# SSB_Transceiver_TX-RX-Switch.net
KiCad netlist of a schematic drawn in EAGLE
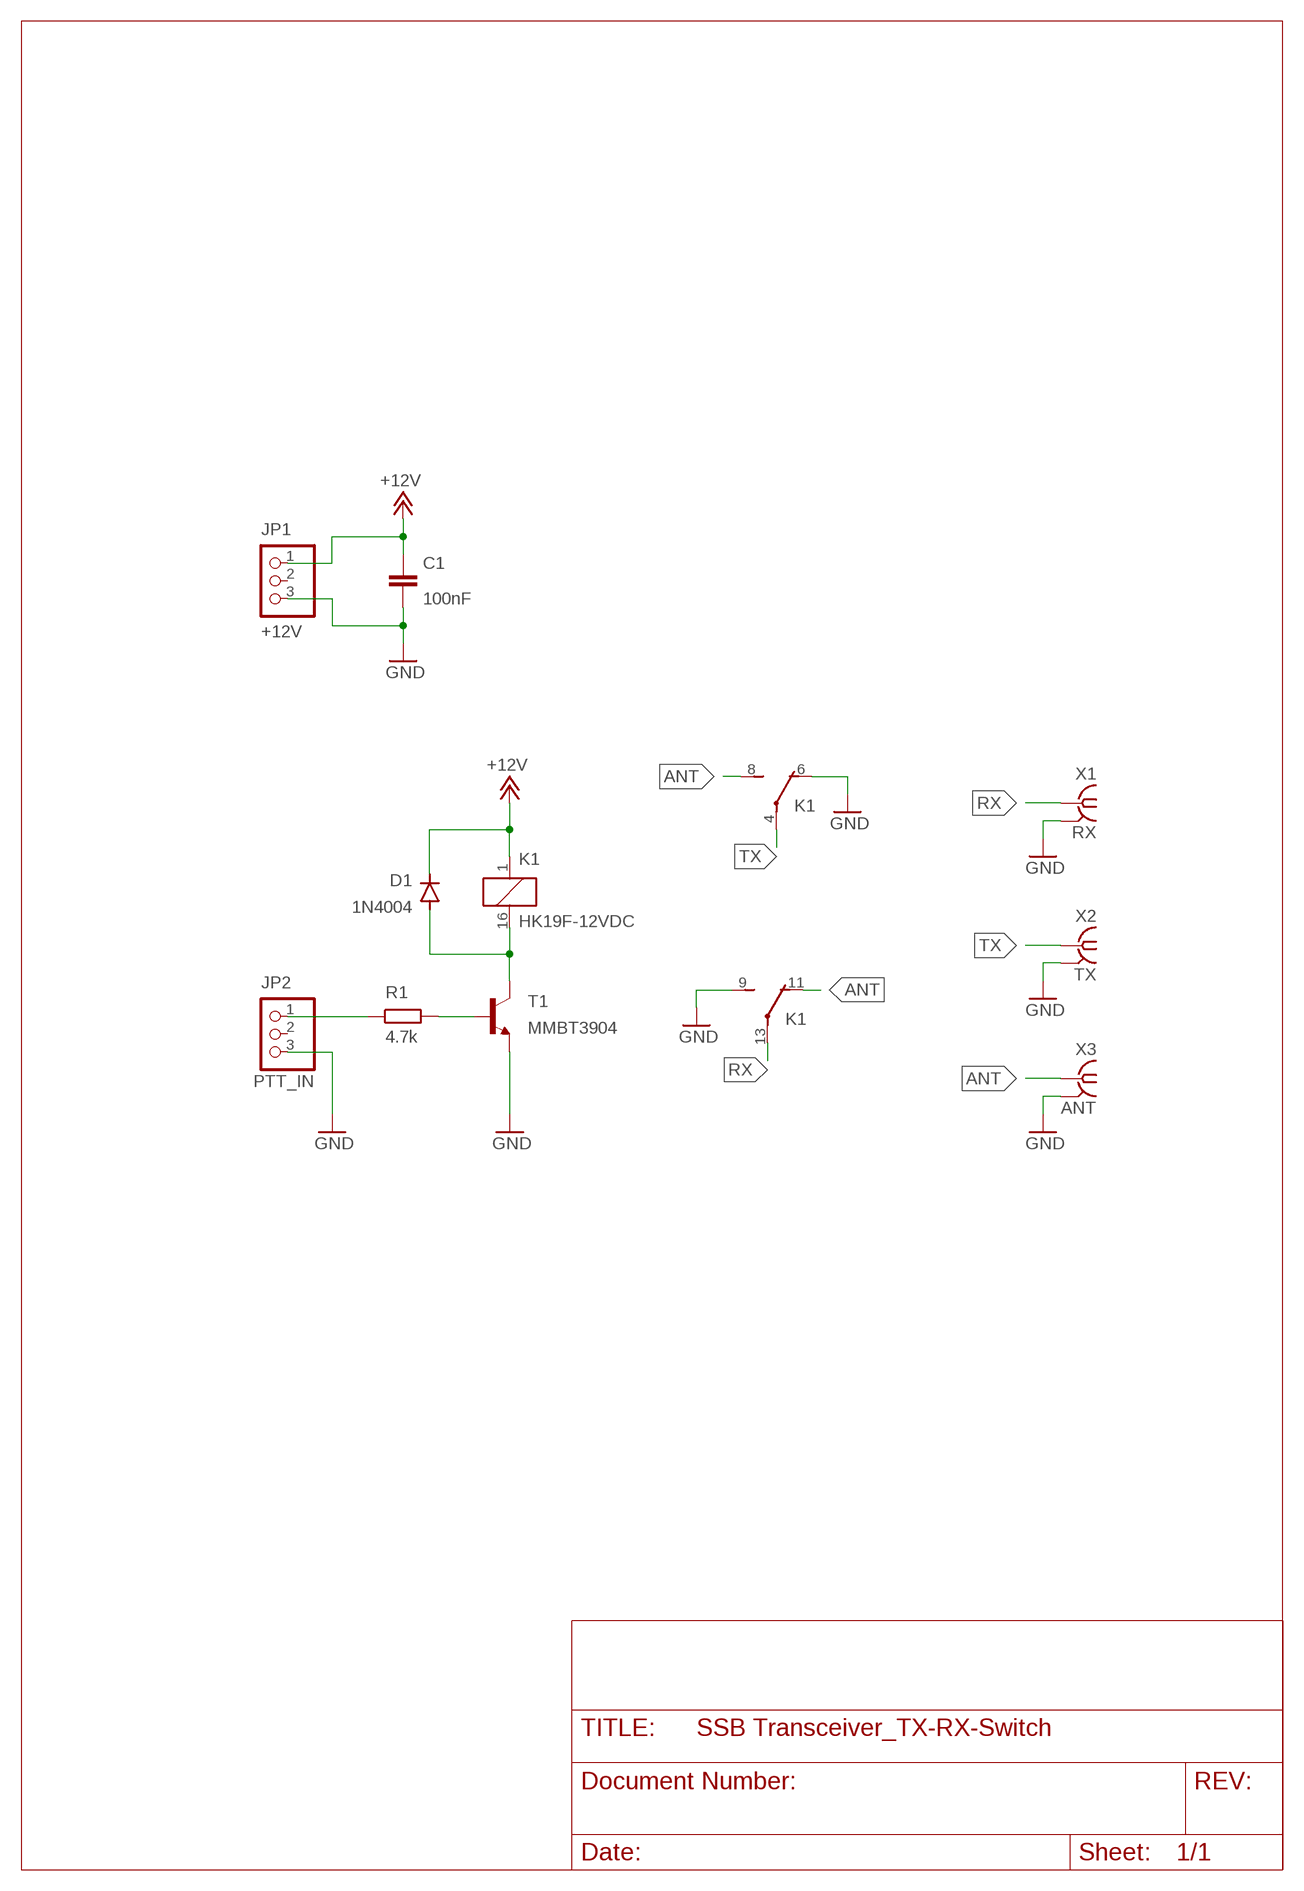
[diagram p0: schematic, sheet 1]

(export (version "E")
  (design (tool "Eeschema 10.0.6"))
  (components
    (comp (ref "C1")
      (value "100nF")
      (footprint "eagle-import:C0805K")
      (libsource (lib "eagle-import") (part "C-EUC0805K"))
    )
    (comp (ref "D1")
      (value "1N4004")
      (footprint "eagle-import:DO41-10")
      (libsource (lib "eagle-import") (part "1N4004"))
    )
    (comp (ref "JP1")
      (value "+12V")
      (footprint "eagle-import:1X03")
      (libsource (lib "eagle-import") (part "PINHD-1X3"))
    )
    (comp (ref "JP2")
      (value "PTT_IN")
      (footprint "eagle-import:1X03")
      (libsource (lib "eagle-import") (part "PINHD-1X3"))
    )
    (comp (ref "K1")
      (value "HK19F-12VDC")
      (footprint "eagle-import:HK19F-12VDC")
      (libsource (lib "eagle-import") (part "HK19F-12VDC"))
    )
    (comp (ref "R1")
      (value "4.7k")
      (footprint "eagle-import:R0805")
      (libsource (lib "eagle-import") (part "R-EU_R0805"))
    )
    (comp (ref "T1")
      (value "MMBT3904")
      (footprint "eagle-import:SOT23-BEC")
      (libsource (lib "eagle-import") (part "-NPN-SOT23-BECMMBT3904LT1"))
    )
    (comp (ref "X1")
      (value "RX")
      (footprint "eagle-import:J502-ND-142-0711-821_826_BOTTOM")
      (libsource (lib "eagle-import") (part "SMA-PCB-CON"))
    )
    (comp (ref "X2")
      (value "TX")
      (footprint "eagle-import:J502-ND-142-0711-821_826_BOTTOM")
      (libsource (lib "eagle-import") (part "SMA-PCB-CON"))
    )
    (comp (ref "X3")
      (value "ANT")
      (footprint "eagle-import:J502-ND-142-0711-821_826_BOTTOM")
      (libsource (lib "eagle-import") (part "SMA-PCB-CON"))
    )
  )
  (nets
    (net (code "1") (name "+12V") (class "Default")
      (node (ref "C1") (pin "1") (pinfunction "1_1") (pintype "passive"))
      (node (ref "D1") (pin "C") (pinfunction "C_C") (pintype "passive"))
      (node (ref "JP1") (pin "1") (pinfunction "1_1") (pintype "passive"))
      (node (ref "K1") (pin "1") (pinfunction "A_1") (pintype "passive"))
    )
    (net (code "2") (name "ANT") (class "Default")
      (node (ref "K1") (pin "11") (pinfunction "O_11") (pintype "passive"))
      (node (ref "K1") (pin "8") (pinfunction "S_8") (pintype "passive"))
      (node (ref "X3") (pin "RF") (pinfunction "RF_RF") (pintype "passive"))
    )
    (net (code "3") (name "GND") (class "Default")
      (node (ref "C1") (pin "2") (pinfunction "2_2") (pintype "passive"))
      (node (ref "JP1") (pin "3") (pinfunction "3_3") (pintype "passive"))
      (node (ref "JP2") (pin "3") (pinfunction "3_3") (pintype "passive"))
      (node (ref "K1") (pin "6") (pinfunction "O_6") (pintype "passive"))
      (node (ref "K1") (pin "9") (pinfunction "S_9") (pintype "passive"))
      (node (ref "T1") (pin "E") (pinfunction "E_E") (pintype "passive"))
      (node (ref "X1") (pin "G@1") (pinfunction "GND_G@1") (pintype "passive"))
      (node (ref "X1") (pin "G@2") (pinfunction "GND_G@2") (pintype "passive"))
      (node (ref "X2") (pin "G@1") (pinfunction "GND_G@1") (pintype "passive"))
      (node (ref "X2") (pin "G@2") (pinfunction "GND_G@2") (pintype "passive"))
      (node (ref "X3") (pin "G@1") (pinfunction "GND_G@1") (pintype "passive"))
      (node (ref "X3") (pin "G@2") (pinfunction "GND_G@2") (pintype "passive"))
    )
    (net (code "4") (name "Net-(JP2-Pad1)") (class "Default")
      (node (ref "JP2") (pin "1") (pinfunction "1_1") (pintype "passive"))
      (node (ref "R1") (pin "1") (pinfunction "1_1") (pintype "passive"))
    )
    (net (code "5") (name "Net-(K1A-B)") (class "Default")
      (node (ref "D1") (pin "A") (pinfunction "A_A") (pintype "passive"))
      (node (ref "K1") (pin "16") (pinfunction "B_16") (pintype "passive"))
      (node (ref "T1") (pin "C") (pinfunction "C_C") (pintype "passive"))
    )
    (net (code "6") (name "Net-(R1-Pad2)") (class "Default")
      (node (ref "R1") (pin "2") (pinfunction "2_2") (pintype "passive"))
      (node (ref "T1") (pin "B") (pinfunction "B_B") (pintype "passive"))
    )
    (net (code "7") (name "RX") (class "Default")
      (node (ref "K1") (pin "13") (pinfunction "P_13") (pintype "passive"))
      (node (ref "X1") (pin "RF") (pinfunction "RF_RF") (pintype "passive"))
    )
    (net (code "8") (name "TX") (class "Default")
      (node (ref "K1") (pin "4") (pinfunction "P_4") (pintype "passive"))
      (node (ref "X2") (pin "RF") (pinfunction "RF_RF") (pintype "passive"))
    )
    (net (code "9") (name "unconnected-(JP1-Pad2)") (class "Default")
      (node (ref "JP1") (pin "2") (pinfunction "2_2") (pintype "passive"))
    )
    (net (code "10") (name "unconnected-(JP2-Pad2)") (class "Default")
      (node (ref "JP2") (pin "2") (pinfunction "2_2") (pintype "passive"))
    )
  )
)
